# 13_-FPGA_Bank_6_Interface.net
KiCad netlist of a schematic drawn in Altium Designer
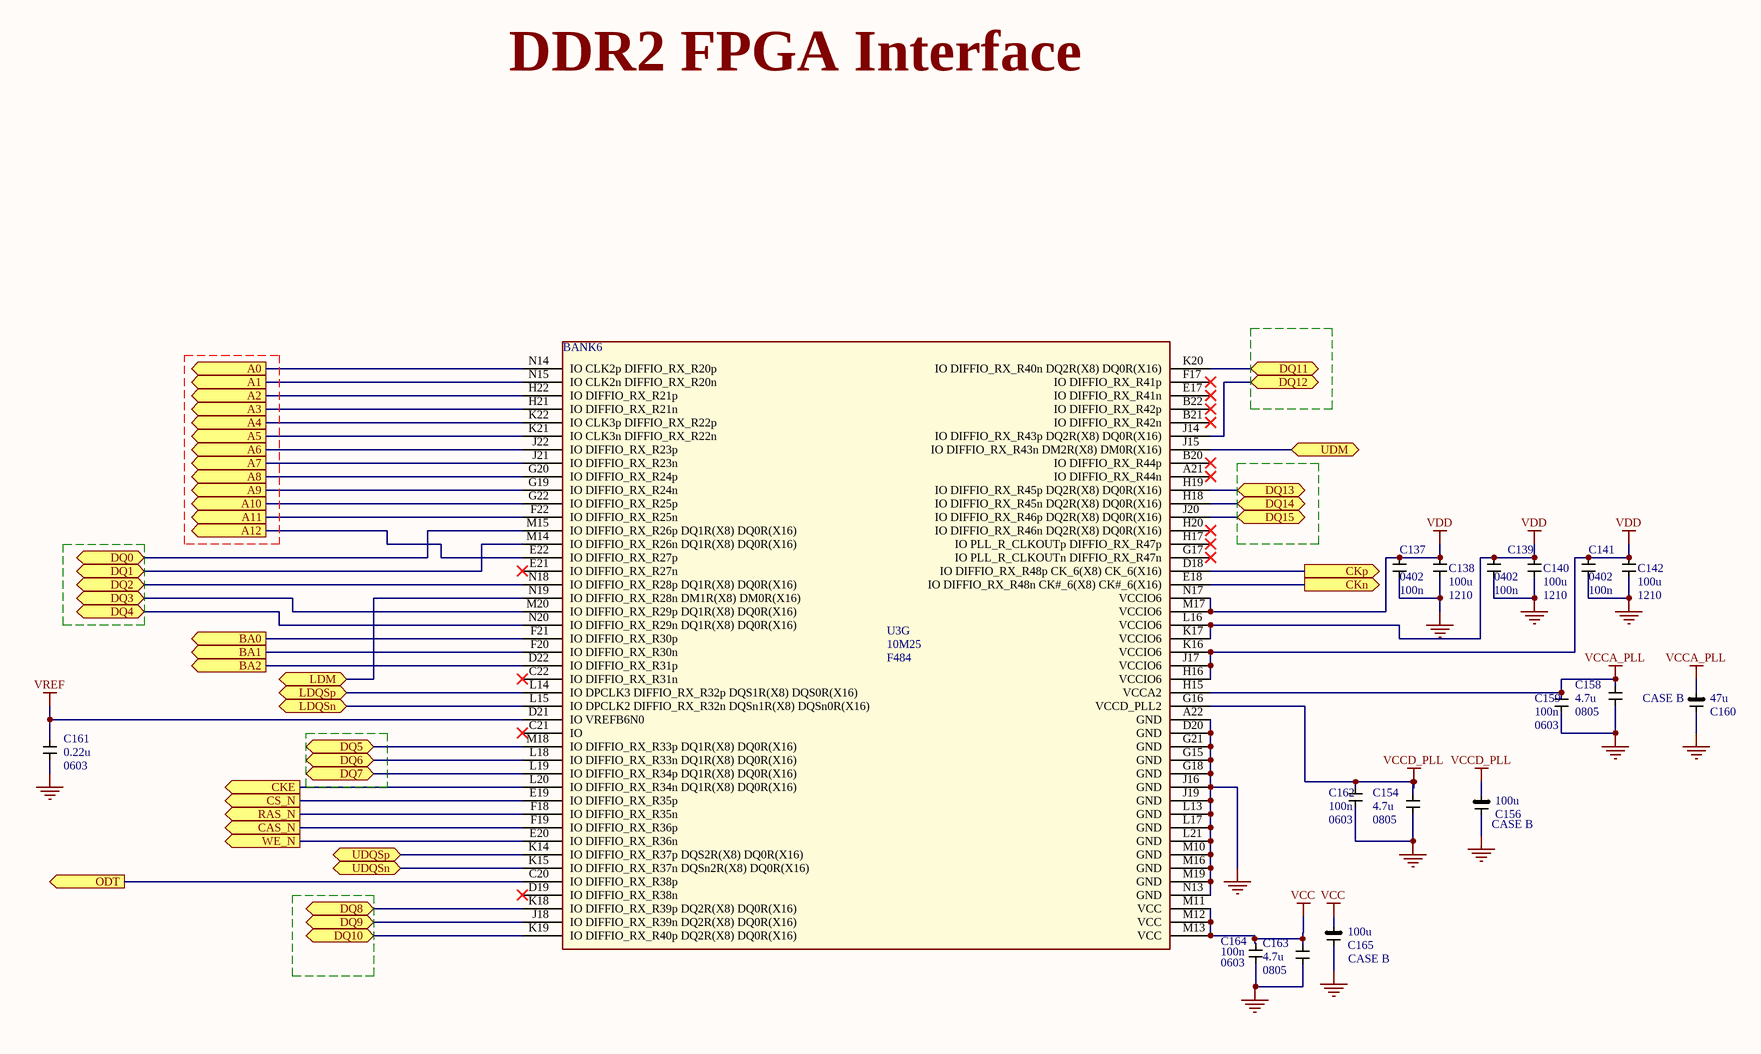
[diagram p0: [13]-FPGA_Bank_6_Interface.SchDoc]

(export (version "E")
  (design (tool "Eeschema 10.0.6"))
  (components
    (comp (ref "C137")
      (value "100n")
      (fields (field (name "ALTIUM_UNNAMED_1") "0402"))
      (libsource (lib "04023C104KAT2A") (part "Component_1"))
    )
    (comp (ref "C138")
      (value "100u")
      (footprint "CAPC3225X28N")
      (fields (field (name "PCB PACKAGE TYPE") "1210"))
      (libsource (lib "1210") (part "Component_1"))
    )
    (comp (ref "C139")
      (value "100n")
      (fields (field (name "ALTIUM_UNNAMED_1") "0402"))
      (libsource (lib "04023C104KAT2A") (part "Component_1"))
    )
    (comp (ref "C140")
      (value "100u")
      (footprint "CAPC3225X28N")
      (fields (field (name "PCB PACKAGE TYPE") "1210"))
      (libsource (lib "1210") (part "Component_1"))
    )
    (comp (ref "C141")
      (value "100n")
      (fields (field (name "ALTIUM_UNNAMED_1") "0402"))
      (libsource (lib "04023C104KAT2A") (part "Component_1"))
    )
    (comp (ref "C142")
      (value "100u")
      (footprint "CAPC3225X28N")
      (fields (field (name "PCB PACKAGE TYPE") "1210"))
      (libsource (lib "1210") (part "Component_1"))
    )
    (comp (ref "C154")
      (value "4.7u")
      (fields (field (name "PCB FOOTPRINT") "0805"))
      (libsource (lib "06031C104KAT2A") (part "Component_1"))
    )
    (comp (ref "C156")
      (value "100u")
      (footprint "CAPC3529X21N")
      (fields (field (name "CASE") "CASE B"))
      (libsource (lib "TAJB107K006TNJ") (part "Component_1"))
    )
    (comp (ref "C158")
      (value "4.7u")
      (fields (field (name "PCB FOOTPRINT") "0805"))
      (libsource (lib "06031C104KAT2A") (part "Component_1"))
    )
    (comp (ref "C159")
      (value "100n")
      (footprint "*0603")
      (fields (field (name "PCB LAYER:") "0603"))
      (libsource (lib "0603YC105KAT2A") (part "Component_1"))
    )
    (comp (ref "C160")
      (value "47u")
      (footprint "CAPC3529X21N")
      (fields (field (name "CASE") "CASE B"))
      (libsource (lib "TAJB107K006TNJ") (part "Component_1"))
    )
    (comp (ref "C161")
      (value "0.22u")
      (footprint "*0603")
      (fields (field (name "PCB LAYER:") "0603"))
      (libsource (lib "0603YC105KAT2A") (part "Component_1"))
    )
    (comp (ref "C162")
      (value "100n")
      (footprint "*0603")
      (fields (field (name "PCB LAYER:") "0603"))
      (libsource (lib "0603YC105KAT2A") (part "Component_1"))
    )
    (comp (ref "C163")
      (value "4.7u")
      (fields (field (name "PCB FOOTPRINT") "0805"))
      (libsource (lib "06031C104KAT2A") (part "Component_1"))
    )
    (comp (ref "C164")
      (value "100n")
      (footprint "*0603")
      (fields (field (name "PCB LAYER:") "0603"))
      (libsource (lib "0603YC105KAT2A") (part "Component_1"))
    )
    (comp (ref "C165")
      (value "100u")
      (footprint "CAPC3529X21N")
      (fields (field (name "CASE") "CASE B"))
      (libsource (lib "TAJB107K006TNJ") (part "Component_1"))
    )
    (comp (ref "U3")
      (value "10M25")
      (footprint "*BGA484C100P22X22_2300X2300X200N")
      (fields (field (name "PART NO.") "10M25DAF484I7G") (field (name "PACKAGE TYPE") "F484"))
      (libsource (lib "10M25DAF484I7G") (part "Component_1"))
    )
  )
  (nets
    (net (code "1") (name "/A0") (class "Default")
      (node (ref "U3") (pin "N14") (pinfunction "IO_CLK2p_DIFFIO_RX_R20p_N14") (pintype "passive"))
    )
    (net (code "2") (name "/A1") (class "Default")
      (node (ref "U3") (pin "N15") (pinfunction "IO_CLK2n_DIFFIO_RX_R20n_N15") (pintype "passive"))
    )
    (net (code "3") (name "/A2") (class "Default")
      (node (ref "U3") (pin "H22") (pinfunction "IO_DIFFIO_RX_R21p_H22") (pintype "passive"))
    )
    (net (code "4") (name "/A3") (class "Default")
      (node (ref "U3") (pin "H21") (pinfunction "IO_DIFFIO_RX_R21n_H21") (pintype "passive"))
    )
    (net (code "5") (name "/A4") (class "Default")
      (node (ref "U3") (pin "K22") (pinfunction "IO_CLK3p_DIFFIO_RX_R22p_K22") (pintype "passive"))
    )
    (net (code "6") (name "/A5") (class "Default")
      (node (ref "U3") (pin "K21") (pinfunction "IO_CLK3n_DIFFIO_RX_R22n_K21") (pintype "passive"))
    )
    (net (code "7") (name "/A6") (class "Default")
      (node (ref "U3") (pin "J22") (pinfunction "IO_DIFFIO_RX_R23p_J22") (pintype "passive"))
    )
    (net (code "8") (name "/A7") (class "Default")
      (node (ref "U3") (pin "J21") (pinfunction "IO_DIFFIO_RX_R23n_J21") (pintype "passive"))
    )
    (net (code "9") (name "/A8") (class "Default")
      (node (ref "U3") (pin "G20") (pinfunction "IO_DIFFIO_RX_R24p_G20") (pintype "passive"))
    )
    (net (code "10") (name "/A9") (class "Default")
      (node (ref "U3") (pin "G19") (pinfunction "IO_DIFFIO_RX_R24n_G19") (pintype "passive"))
    )
    (net (code "11") (name "/A10") (class "Default")
      (node (ref "U3") (pin "G22") (pinfunction "IO_DIFFIO_RX_R25p_G22") (pintype "passive"))
    )
    (net (code "12") (name "/A11") (class "Default")
      (node (ref "U3") (pin "F22") (pinfunction "IO_DIFFIO_RX_R25n_F22") (pintype "passive"))
    )
    (net (code "13") (name "/A12") (class "Default")
      (node (ref "U3") (pin "E22") (pinfunction "IO_DIFFIO_RX_R27p_E22") (pintype "passive"))
    )
    (net (code "14") (name "/BA0") (class "Default")
      (node (ref "U3") (pin "F21") (pinfunction "IO_DIFFIO_RX_R30p_F21") (pintype "passive"))
    )
    (net (code "15") (name "/BA1") (class "Default")
      (node (ref "U3") (pin "F20") (pinfunction "IO_DIFFIO_RX_R30n_F20") (pintype "passive"))
    )
    (net (code "16") (name "/BA2") (class "Default")
      (node (ref "U3") (pin "D22") (pinfunction "IO_DIFFIO_RX_R31p_D22") (pintype "passive"))
    )
    (net (code "17") (name "/CAS_N") (class "Default")
      (node (ref "U3") (pin "F19") (pinfunction "IO_DIFFIO_RX_R36p_F19") (pintype "passive"))
    )
    (net (code "18") (name "/CKE") (class "Default")
      (node (ref "U3") (pin "L20") (pinfunction "IO_DIFFIO_RX_R34n_DQ1R(X8)_DQ0R(X16)_L20") (pintype "passive"))
    )
    (net (code "19") (name "/CKn") (class "Default")
      (node (ref "U3") (pin "E18") (pinfunction "IO_DIFFIO_RX_R48n_CK#_6(X8)_CK#_6(X16)_E18") (pintype "passive"))
    )
    (net (code "20") (name "/CKp") (class "Default")
      (node (ref "U3") (pin "D18") (pinfunction "IO_DIFFIO_RX_R48p_CK_6(X8)_CK_6(X16)_D18") (pintype "passive"))
    )
    (net (code "21") (name "/CS_N") (class "Default")
      (node (ref "U3") (pin "E19") (pinfunction "IO_DIFFIO_RX_R35p_E19") (pintype "passive"))
    )
    (net (code "22") (name "/DQ0") (class "Default")
      (node (ref "U3") (pin "M15") (pinfunction "IO_DIFFIO_RX_R26p_DQ1R(X8)_DQ0R(X16)_M15") (pintype "passive"))
    )
    (net (code "23") (name "/DQ1") (class "Default")
      (node (ref "U3") (pin "M14") (pinfunction "IO_DIFFIO_RX_R26n_DQ1R(X8)_DQ0R(X16)_M14") (pintype "passive"))
    )
    (net (code "24") (name "/DQ2") (class "Default")
      (node (ref "U3") (pin "N18") (pinfunction "IO_DIFFIO_RX_R28p_DQ1R(X8)_DQ0R(X16)_N18") (pintype "passive"))
    )
    (net (code "25") (name "/DQ3") (class "Default")
      (node (ref "U3") (pin "M20") (pinfunction "IO_DIFFIO_RX_R29p_DQ1R(X8)_DQ0R(X16)_M20") (pintype "passive"))
    )
    (net (code "26") (name "/DQ4") (class "Default")
      (node (ref "U3") (pin "N20") (pinfunction "IO_DIFFIO_RX_R29n_DQ1R(X8)_DQ0R(X16)_N20") (pintype "passive"))
    )
    (net (code "27") (name "/DQ5") (class "Default")
      (node (ref "U3") (pin "M18") (pinfunction "IO_DIFFIO_RX_R33p_DQ1R(X8)_DQ0R(X16)_M18") (pintype "passive"))
    )
    (net (code "28") (name "/DQ6") (class "Default")
      (node (ref "U3") (pin "L18") (pinfunction "IO_DIFFIO_RX_R33n_DQ1R(X8)_DQ0R(X16)_L18") (pintype "passive"))
    )
    (net (code "29") (name "/DQ7") (class "Default")
      (node (ref "U3") (pin "L19") (pinfunction "IO_DIFFIO_RX_R34p_DQ1R(X8)_DQ0R(X16)_L19") (pintype "passive"))
    )
    (net (code "30") (name "/DQ8") (class "Default")
      (node (ref "U3") (pin "K18") (pinfunction "IO_DIFFIO_RX_R39p_DQ2R(X8)_DQ0R(X16)_K18") (pintype "passive"))
    )
    (net (code "31") (name "/DQ9") (class "Default")
      (node (ref "U3") (pin "J18") (pinfunction "IO_DIFFIO_RX_R39n_DQ2R(X8)_DQ0R(X16)_J18") (pintype "passive"))
    )
    (net (code "32") (name "/DQ10") (class "Default")
      (node (ref "U3") (pin "K19") (pinfunction "IO_DIFFIO_RX_R40p_DQ2R(X8)_DQ0R(X16)_K19") (pintype "passive"))
    )
    (net (code "33") (name "/DQ11") (class "Default")
      (node (ref "U3") (pin "K20") (pinfunction "IO_DIFFIO_RX_R40n_DQ2R(X8)_DQ0R(X16)_K20") (pintype "passive"))
    )
    (net (code "34") (name "/DQ12") (class "Default")
      (node (ref "U3") (pin "J14") (pinfunction "IO_DIFFIO_RX_R43p_DQ2R(X8)_DQ0R(X16)_J14") (pintype "passive"))
    )
    (net (code "35") (name "/DQ13") (class "Default")
      (node (ref "U3") (pin "H19") (pinfunction "IO_DIFFIO_RX_R45p_DQ2R(X8)_DQ0R(X16)_H19") (pintype "passive"))
    )
    (net (code "36") (name "/DQ14") (class "Default")
      (node (ref "U3") (pin "H18") (pinfunction "IO_DIFFIO_RX_R45n_DQ2R(X8)_DQ0R(X16)_H18") (pintype "passive"))
    )
    (net (code "37") (name "/DQ15") (class "Default")
      (node (ref "U3") (pin "J20") (pinfunction "IO_DIFFIO_RX_R46p_DQ2R(X8)_DQ0R(X16)_J20") (pintype "passive"))
    )
    (net (code "38") (name "/LDM") (class "Default")
      (node (ref "U3") (pin "N19") (pinfunction "IO_DIFFIO_RX_R28n_DM1R(X8)_DM0R(X16)_N19") (pintype "passive"))
    )
    (net (code "39") (name "/LDQSn") (class "Default")
      (node (ref "U3") (pin "L15") (pinfunction "IO_DPCLK2_DIFFIO_RX_R32n_DQSn1R(X8)_DQSn0R(X16)_L15") (pintype "passive"))
    )
    (net (code "40") (name "/LDQSp") (class "Default")
      (node (ref "U3") (pin "L14") (pinfunction "IO_DPCLK3_DIFFIO_RX_R32p_DQS1R(X8)_DQS0R(X16)_L14") (pintype "passive"))
    )
    (net (code "41") (name "/ODT") (class "Default")
      (node (ref "U3") (pin "C20") (pinfunction "IO_DIFFIO_RX_R38p_C20") (pintype "passive"))
    )
    (net (code "42") (name "/RAS_N") (class "Default")
      (node (ref "U3") (pin "F18") (pinfunction "IO_DIFFIO_RX_R35n_F18") (pintype "passive"))
    )
    (net (code "43") (name "/UDM") (class "Default")
      (node (ref "U3") (pin "J15") (pinfunction "IO_DIFFIO_RX_R43n_DM2R(X8)_DM0R(X16)_J15") (pintype "passive"))
    )
    (net (code "44") (name "/UDQSn") (class "Default")
      (node (ref "U3") (pin "K15") (pinfunction "IO_DIFFIO_RX_R37n_DQSn2R(X8)_DQ0R(X16)_K15") (pintype "passive"))
    )
    (net (code "45") (name "/UDQSp") (class "Default")
      (node (ref "U3") (pin "K14") (pinfunction "IO_DIFFIO_RX_R37p_DQS2R(X8)_DQ0R(X16)_K14") (pintype "passive"))
    )
    (net (code "46") (name "/WE_N") (class "Default")
      (node (ref "U3") (pin "E20") (pinfunction "IO_DIFFIO_RX_R36n_E20") (pintype "passive"))
    )
    (net (code "47") (name "GND") (class "Default")
      (node (ref "C137") (pin "1") (pinfunction "1_1") (pintype "passive"))
      (node (ref "C138") (pin "1") (pinfunction "1_1") (pintype "passive"))
      (node (ref "C139") (pin "1") (pinfunction "1_1") (pintype "passive"))
      (node (ref "C140") (pin "1") (pinfunction "1_1") (pintype "passive"))
      (node (ref "C141") (pin "1") (pinfunction "1_1") (pintype "passive"))
      (node (ref "C142") (pin "1") (pinfunction "1_1") (pintype "passive"))
      (node (ref "C154") (pin "1") (pinfunction "1_1") (pintype "passive"))
      (node (ref "C156") (pin "2") (pinfunction "2_2") (pintype "passive"))
      (node (ref "C158") (pin "1") (pinfunction "1_1") (pintype "passive"))
      (node (ref "C159") (pin "1") (pinfunction "1_1") (pintype "passive"))
      (node (ref "C160") (pin "2") (pinfunction "2_2") (pintype "passive"))
      (node (ref "C161") (pin "1") (pinfunction "1_1") (pintype "passive"))
      (node (ref "C162") (pin "1") (pinfunction "1_1") (pintype "passive"))
      (node (ref "C163") (pin "1") (pinfunction "1_1") (pintype "passive"))
      (node (ref "C164") (pin "1") (pinfunction "1_1") (pintype "passive"))
      (node (ref "C165") (pin "2") (pinfunction "2_2") (pintype "passive"))
      (node (ref "U3") (pin "A22") (pinfunction "GND_A22") (pintype "passive"))
      (node (ref "U3") (pin "D20") (pinfunction "GND_D20") (pintype "passive"))
      (node (ref "U3") (pin "G15") (pinfunction "GND_G15") (pintype "passive"))
      (node (ref "U3") (pin "G18") (pinfunction "GND_G18") (pintype "passive"))
      (node (ref "U3") (pin "G21") (pinfunction "GND_G21") (pintype "passive"))
      (node (ref "U3") (pin "J16") (pinfunction "GND_J16") (pintype "passive"))
      (node (ref "U3") (pin "J19") (pinfunction "GND_J19") (pintype "passive"))
      (node (ref "U3") (pin "L13") (pinfunction "GND_L13") (pintype "passive"))
      (node (ref "U3") (pin "L17") (pinfunction "GND_L17") (pintype "passive"))
      (node (ref "U3") (pin "L21") (pinfunction "GND_L21") (pintype "passive"))
      (node (ref "U3") (pin "M10") (pinfunction "GND_M10") (pintype "passive"))
      (node (ref "U3") (pin "M16") (pinfunction "GND_M16") (pintype "passive"))
      (node (ref "U3") (pin "M19") (pinfunction "GND_M19") (pintype "passive"))
      (node (ref "U3") (pin "N13") (pinfunction "GND_N13") (pintype "passive"))
    )
    (net (code "48") (name "VCC") (class "Default")
      (node (ref "C163") (pin "2") (pinfunction "2_2") (pintype "passive"))
      (node (ref "C164") (pin "2") (pinfunction "2_2") (pintype "passive"))
      (node (ref "C165") (pin "1") (pinfunction "1_1") (pintype "passive"))
      (node (ref "U3") (pin "M11") (pinfunction "VCC_M11") (pintype "passive"))
      (node (ref "U3") (pin "M12") (pinfunction "VCC_M12") (pintype "passive"))
      (node (ref "U3") (pin "M13") (pinfunction "VCC_M13") (pintype "passive"))
    )
    (net (code "49") (name "VCCA_PLL") (class "Default")
      (node (ref "C158") (pin "2") (pinfunction "2_2") (pintype "passive"))
      (node (ref "C159") (pin "2") (pinfunction "2_2") (pintype "passive"))
      (node (ref "C160") (pin "1") (pinfunction "1_1") (pintype "passive"))
      (node (ref "U3") (pin "H15") (pinfunction "VCCA2_H15") (pintype "passive"))
    )
    (net (code "50") (name "VCCD_PLL") (class "Default")
      (node (ref "C154") (pin "2") (pinfunction "2_2") (pintype "passive"))
      (node (ref "C156") (pin "1") (pinfunction "1_1") (pintype "passive"))
      (node (ref "C162") (pin "2") (pinfunction "2_2") (pintype "passive"))
      (node (ref "U3") (pin "G16") (pinfunction "VCCD_PLL2_G16") (pintype "passive"))
    )
    (net (code "51") (name "VDD") (class "Default")
      (node (ref "C137") (pin "2") (pinfunction "2_2") (pintype "passive"))
      (node (ref "C138") (pin "2") (pinfunction "2_2") (pintype "passive"))
      (node (ref "C139") (pin "2") (pinfunction "2_2") (pintype "passive"))
      (node (ref "C140") (pin "2") (pinfunction "2_2") (pintype "passive"))
      (node (ref "C141") (pin "2") (pinfunction "2_2") (pintype "passive"))
      (node (ref "C142") (pin "2") (pinfunction "2_2") (pintype "passive"))
      (node (ref "U3") (pin "H16") (pinfunction "VCCIO6_H16") (pintype "passive"))
      (node (ref "U3") (pin "J17") (pinfunction "VCCIO6_J17") (pintype "passive"))
      (node (ref "U3") (pin "K16") (pinfunction "VCCIO6_K16") (pintype "passive"))
      (node (ref "U3") (pin "K17") (pinfunction "VCCIO6_K17") (pintype "passive"))
      (node (ref "U3") (pin "L16") (pinfunction "VCCIO6_L16") (pintype "passive"))
      (node (ref "U3") (pin "M17") (pinfunction "VCCIO6_M17") (pintype "passive"))
      (node (ref "U3") (pin "N17") (pinfunction "VCCIO6_N17") (pintype "passive"))
    )
    (net (code "52") (name "VREF") (class "Default")
      (node (ref "C161") (pin "2") (pinfunction "2_2") (pintype "passive"))
      (node (ref "U3") (pin "D21") (pinfunction "IO_VREFB6N0_D21") (pintype "passive"))
    )
    (net (code "53") (name "unconnected-(U3G-IO-PadC21)") (class "Default")
      (node (ref "U3") (pin "C21") (pinfunction "IO_C21") (pintype "passive+no_connect"))
    )
    (net (code "54") (name "unconnected-(U3G-IO_DIFFIO_RX_R27n-PadE21)") (class "Default")
      (node (ref "U3") (pin "E21") (pinfunction "IO_DIFFIO_RX_R27n_E21") (pintype "passive+no_connect"))
    )
    (net (code "55") (name "unconnected-(U3G-IO_DIFFIO_RX_R31n-PadC22)") (class "Default")
      (node (ref "U3") (pin "C22") (pinfunction "IO_DIFFIO_RX_R31n_C22") (pintype "passive+no_connect"))
    )
    (net (code "56") (name "unconnected-(U3G-IO_DIFFIO_RX_R38n-PadD19)") (class "Default")
      (node (ref "U3") (pin "D19") (pinfunction "IO_DIFFIO_RX_R38n_D19") (pintype "passive+no_connect"))
    )
    (net (code "57") (name "unconnected-(U3G-IO_DIFFIO_RX_R41n-PadE17)") (class "Default")
      (node (ref "U3") (pin "E17") (pinfunction "IO_DIFFIO_RX_R41n_E17") (pintype "passive+no_connect"))
    )
    (net (code "58") (name "unconnected-(U3G-IO_DIFFIO_RX_R41p-PadF17)") (class "Default")
      (node (ref "U3") (pin "F17") (pinfunction "IO_DIFFIO_RX_R41p_F17") (pintype "passive+no_connect"))
    )
    (net (code "59") (name "unconnected-(U3G-IO_DIFFIO_RX_R42n-PadB21)") (class "Default")
      (node (ref "U3") (pin "B21") (pinfunction "IO_DIFFIO_RX_R42n_B21") (pintype "passive+no_connect"))
    )
    (net (code "60") (name "unconnected-(U3G-IO_DIFFIO_RX_R42p-PadB22)") (class "Default")
      (node (ref "U3") (pin "B22") (pinfunction "IO_DIFFIO_RX_R42p_B22") (pintype "passive+no_connect"))
    )
    (net (code "61") (name "unconnected-(U3G-IO_DIFFIO_RX_R44n-PadA21)") (class "Default")
      (node (ref "U3") (pin "A21") (pinfunction "IO_DIFFIO_RX_R44n_A21") (pintype "passive+no_connect"))
    )
    (net (code "62") (name "unconnected-(U3G-IO_DIFFIO_RX_R44p-PadB20)") (class "Default")
      (node (ref "U3") (pin "B20") (pinfunction "IO_DIFFIO_RX_R44p_B20") (pintype "passive+no_connect"))
    )
    (net (code "63") (name "unconnected-(U3G-IO_DIFFIO_RX_R46n_DQ2R(X8)_DQ0R(X16)-PadH20)") (class "Default")
      (node (ref "U3") (pin "H20") (pinfunction "IO_DIFFIO_RX_R46n_DQ2R(X8)_DQ0R(X16)_H20") (pintype "passive+no_connect"))
    )
    (net (code "64") (name "unconnected-(U3G-IO_PLL_R_CLKOUTn_DIFFIO_RX_R47n-PadG17)") (class "Default")
      (node (ref "U3") (pin "G17") (pinfunction "IO_PLL_R_CLKOUTn_DIFFIO_RX_R47n_G17") (pintype "passive+no_connect"))
    )
    (net (code "65") (name "unconnected-(U3G-IO_PLL_R_CLKOUTp_DIFFIO_RX_R47p-PadH17)") (class "Default")
      (node (ref "U3") (pin "H17") (pinfunction "IO_PLL_R_CLKOUTp_DIFFIO_RX_R47p_H17") (pintype "passive+no_connect"))
    )
  )
)
